# LNA.net
KiCad netlist of a schematic drawn in EAGLE
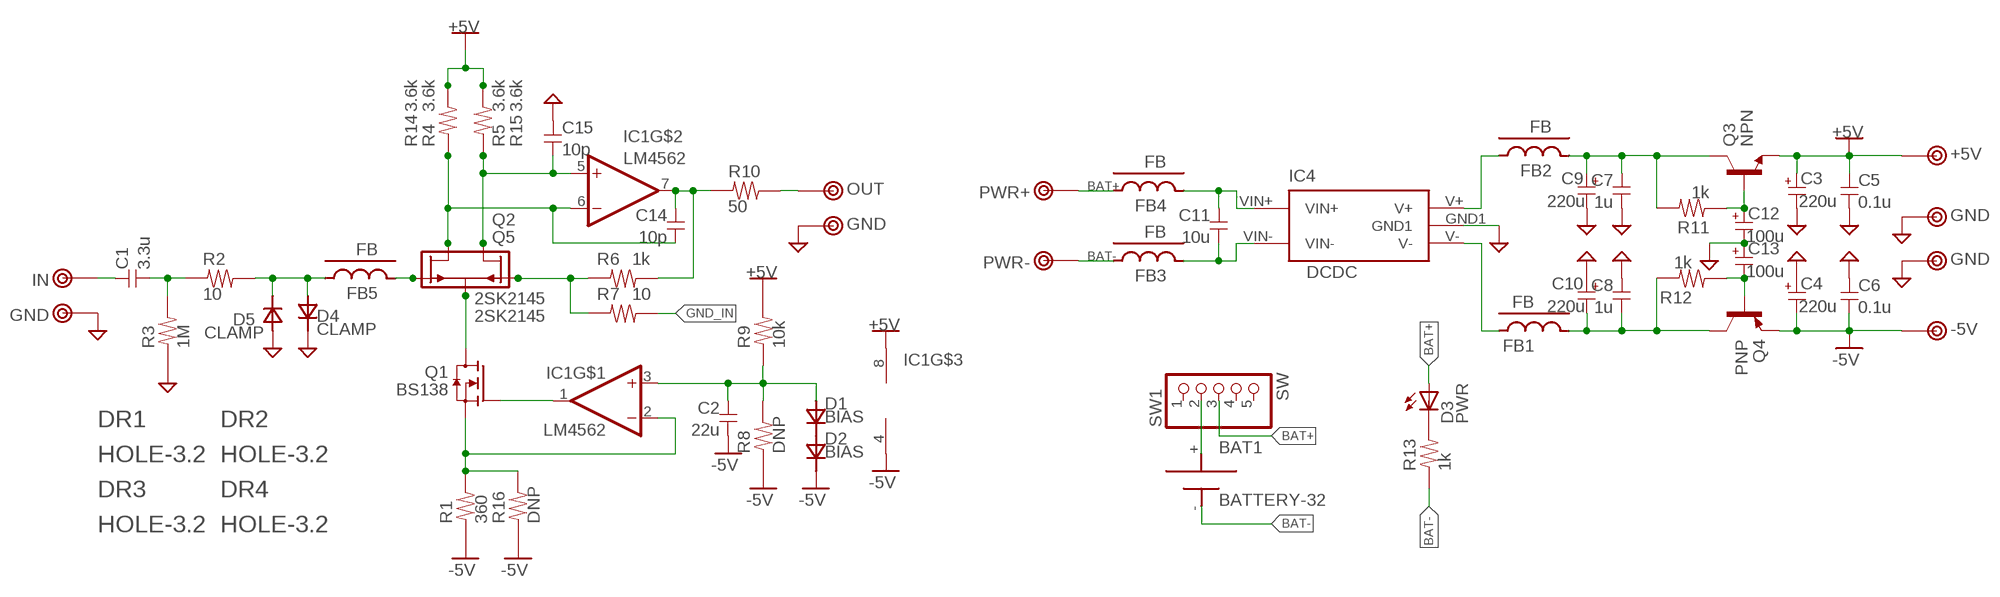
[diagram p0: schematic, sheet 1]

(export (version "E")
  (design (tool "Eeschema 10.0.6"))
  (components
    (comp (ref "BAT1")
      (value "BATTERY-32")
      (footprint "eagle-import:BH-321")
      (libsource (lib "eagle-import") (part "BATTERY-32"))
    )
    (comp (ref "C1")
      (value "3.3u")
      (footprint "eagle-import:3225")
      (libsource (lib "eagle-import") (part "C-3225"))
    )
    (comp (ref "C2")
      (value "22u")
      (footprint "eagle-import:3225")
      (libsource (lib "eagle-import") (part "C-3225"))
    )
    (comp (ref "C3")
      (value "220u")
      (footprint "eagle-import:E2,5-8")
      (libsource (lib "eagle-import") (part "CPOLE2.5-8"))
    )
    (comp (ref "C4")
      (value "220u")
      (footprint "eagle-import:E2,5-8")
      (libsource (lib "eagle-import") (part "CPOLE2.5-8"))
    )
    (comp (ref "C5")
      (value "0.1u")
      (footprint "eagle-import:1608C")
      (libsource (lib "eagle-import") (part "C-1608"))
    )
    (comp (ref "C6")
      (value "0.1u")
      (footprint "eagle-import:1608C")
      (libsource (lib "eagle-import") (part "C-1608"))
    )
    (comp (ref "C7")
      (value "1u")
      (footprint "eagle-import:1608C")
      (libsource (lib "eagle-import") (part "C-1608"))
    )
    (comp (ref "C8")
      (value "1u")
      (footprint "eagle-import:1608C")
      (libsource (lib "eagle-import") (part "C-1608"))
    )
    (comp (ref "C9")
      (value "220u")
      (footprint "eagle-import:E2,5-8")
      (libsource (lib "eagle-import") (part "CPOLE2.5-8"))
    )
    (comp (ref "C10")
      (value "220u")
      (footprint "eagle-import:E2,5-8")
      (libsource (lib "eagle-import") (part "CPOLE2.5-8"))
    )
    (comp (ref "C11")
      (value "10u")
      (footprint "eagle-import:2012")
      (libsource (lib "eagle-import") (part "C-2012"))
    )
    (comp (ref "C12")
      (value "100u")
      (footprint "eagle-import:E2.5-6.5")
      (libsource (lib "eagle-import") (part "CPOLE2.5-6.5"))
    )
    (comp (ref "C13")
      (value "100u")
      (footprint "eagle-import:E2.5-6.5")
      (libsource (lib "eagle-import") (part "CPOLE2.5-6.5"))
    )
    (comp (ref "C14")
      (value "10p")
      (footprint "eagle-import:1608C")
      (libsource (lib "eagle-import") (part "C-1608"))
    )
    (comp (ref "C15")
      (value "10p")
      (footprint "eagle-import:1608C")
      (libsource (lib "eagle-import") (part "C-1608"))
    )
    (comp (ref "D1")
      (value "BIAS")
      (footprint "eagle-import:SOD123")
      (libsource (lib "eagle-import") (part "DIODE-1N4148W"))
    )
    (comp (ref "D2")
      (value "BIAS")
      (footprint "eagle-import:SOD123")
      (libsource (lib "eagle-import") (part "DIODE-1N4148W"))
    )
    (comp (ref "D3")
      (value "PWR")
      (footprint "eagle-import:D1608")
      (libsource (lib "eagle-import") (part "LED-SMD1608"))
    )
    (comp (ref "D4")
      (value "CLAMP")
      (footprint "eagle-import:SOD323")
      (libsource (lib "eagle-import") (part "DIODE-323"))
    )
    (comp (ref "D5")
      (value "CLAMP")
      (footprint "eagle-import:SOD323")
      (libsource (lib "eagle-import") (part "DIODE-323"))
    )
    (comp (ref "DR1")
      (value "HOLE-3.2")
      (footprint "eagle-import:HOLE_3.2")
      (libsource (lib "eagle-import") (part "HOLE-3.2"))
    )
    (comp (ref "DR2")
      (value "HOLE-3.2")
      (footprint "eagle-import:HOLE_3.2")
      (libsource (lib "eagle-import") (part "HOLE-3.2"))
    )
    (comp (ref "DR3")
      (value "HOLE-3.2")
      (footprint "eagle-import:HOLE_3.2")
      (libsource (lib "eagle-import") (part "HOLE-3.2"))
    )
    (comp (ref "DR4")
      (value "HOLE-3.2")
      (footprint "eagle-import:HOLE_3.2")
      (libsource (lib "eagle-import") (part "HOLE-3.2"))
    )
    (comp (ref "FB1")
      (value "FB")
      (footprint "eagle-import:1608-FB")
      (libsource (lib "eagle-import") (part "FB-1608FB"))
    )
    (comp (ref "FB2")
      (value "FB")
      (footprint "eagle-import:1608-FB")
      (libsource (lib "eagle-import") (part "FB-1608FB"))
    )
    (comp (ref "FB3")
      (value "FB")
      (footprint "eagle-import:1608-FB")
      (libsource (lib "eagle-import") (part "FB-1608FB"))
    )
    (comp (ref "FB4")
      (value "FB")
      (footprint "eagle-import:1608-FB")
      (libsource (lib "eagle-import") (part "FB-1608FB"))
    )
    (comp (ref "FB5")
      (value "FB")
      (footprint "eagle-import:1608-FB")
      (libsource (lib "eagle-import") (part "FB-1608FB"))
    )
    (comp (ref "IC1")
      (value "LM4562")
      (footprint "eagle-import:SOP8")
      (libsource (lib "eagle-import") (part "OPA-2-SOP"))
    )
    (comp (ref "IC4")
      (value "DCDC")
      (footprint "eagle-import:DCDC2")
      (libsource (lib "eagle-import") (part "DCDC2"))
    )
    (comp (ref "Q1")
      (value "BS138")
      (footprint "eagle-import:SC59")
      (libsource (lib "eagle-import") (part "NMOS-SMD"))
    )
    (comp (ref "Q2")
      (value "2SK2145")
      (footprint "eagle-import:SOT23-5")
      (libsource (lib "eagle-import") (part "JFET-DUAL"))
    )
    (comp (ref "Q3")
      (value "NPN")
      (footprint "eagle-import:SOT223")
      (libsource (lib "eagle-import") (part "NPN-SOT223"))
    )
    (comp (ref "Q4")
      (value "PNP")
      (footprint "eagle-import:SOT223")
      (libsource (lib "eagle-import") (part "PNP-SOT223"))
    )
    (comp (ref "Q5")
      (value "2SK2145")
      (footprint "eagle-import:SOT23-5")
      (libsource (lib "eagle-import") (part "JFET-DUAL"))
    )
    (comp (ref "R1")
      (value "360")
      (footprint "eagle-import:1608")
      (libsource (lib "eagle-import") (part "R-1608"))
    )
    (comp (ref "R2")
      (value "10")
      (footprint "eagle-import:1608")
      (libsource (lib "eagle-import") (part "R-1608"))
    )
    (comp (ref "R3")
      (value "1M")
      (footprint "eagle-import:1608")
      (libsource (lib "eagle-import") (part "R-1608"))
    )
    (comp (ref "R4")
      (value "3.6k")
      (footprint "eagle-import:1608")
      (libsource (lib "eagle-import") (part "R-1608"))
    )
    (comp (ref "R5")
      (value "3.6k")
      (footprint "eagle-import:1608")
      (libsource (lib "eagle-import") (part "R-1608"))
    )
    (comp (ref "R6")
      (value "1k")
      (footprint "eagle-import:1608")
      (libsource (lib "eagle-import") (part "R-1608"))
    )
    (comp (ref "R7")
      (value "10")
      (footprint "eagle-import:1608")
      (libsource (lib "eagle-import") (part "R-1608"))
    )
    (comp (ref "R8")
      (value "DNP")
      (footprint "eagle-import:1608")
      (libsource (lib "eagle-import") (part "R-1608"))
    )
    (comp (ref "R9")
      (value "10k")
      (footprint "eagle-import:1608")
      (libsource (lib "eagle-import") (part "R-1608"))
    )
    (comp (ref "R10")
      (value "50")
      (footprint "eagle-import:1608")
      (libsource (lib "eagle-import") (part "R-1608"))
    )
    (comp (ref "R11")
      (value "1k")
      (footprint "eagle-import:1608")
      (libsource (lib "eagle-import") (part "R-1608"))
    )
    (comp (ref "R12")
      (value "1k")
      (footprint "eagle-import:1608")
      (libsource (lib "eagle-import") (part "R-1608"))
    )
    (comp (ref "R13")
      (value "1k")
      (footprint "eagle-import:1608")
      (libsource (lib "eagle-import") (part "R-1608"))
    )
    (comp (ref "R14")
      (value "3.6k")
      (footprint "eagle-import:1608")
      (libsource (lib "eagle-import") (part "R-1608"))
    )
    (comp (ref "R15")
      (value "3.6k")
      (footprint "eagle-import:1608")
      (libsource (lib "eagle-import") (part "R-1608"))
    )
    (comp (ref "R16")
      (value "DNP")
      (footprint "eagle-import:1608")
      (libsource (lib "eagle-import") (part "R-1608"))
    )
    (comp (ref "SW1")
      (value "SW")
      (footprint "eagle-import:1X05-BIG")
      (libsource (lib "eagle-import") (part "SW-1X5"))
    )
    (comp (ref "TP1")
      (value "IN")
      (footprint "eagle-import:TESTPIN")
      (libsource (lib "eagle-import") (part "TESTPIN"))
    )
    (comp (ref "TP2")
      (value "GND")
      (footprint "eagle-import:TESTPIN")
      (libsource (lib "eagle-import") (part "TESTPIN"))
    )
    (comp (ref "TP3")
      (value "OUT")
      (footprint "eagle-import:TESTPIN")
      (libsource (lib "eagle-import") (part "TESTPIN"))
    )
    (comp (ref "TP4")
      (value "GND")
      (footprint "eagle-import:TESTPIN")
      (libsource (lib "eagle-import") (part "TESTPIN"))
    )
    (comp (ref "TP5")
      (value "PWR+")
      (footprint "eagle-import:TESTPIN")
      (libsource (lib "eagle-import") (part "TESTPIN"))
    )
    (comp (ref "TP6")
      (value "PWR-")
      (footprint "eagle-import:TESTPIN")
      (libsource (lib "eagle-import") (part "TESTPIN"))
    )
    (comp (ref "TP7")
      (value "+5V")
      (footprint "eagle-import:TESTPIN-MID")
      (libsource (lib "eagle-import") (part "TESTPIN-MID"))
    )
    (comp (ref "TP8")
      (value "GND")
      (footprint "eagle-import:TESTPIN-MID")
      (libsource (lib "eagle-import") (part "TESTPIN-MID"))
    )
    (comp (ref "TP9")
      (value "GND")
      (footprint "eagle-import:TESTPIN-MID")
      (libsource (lib "eagle-import") (part "TESTPIN-MID"))
    )
    (comp (ref "TP10")
      (value "-5V")
      (footprint "eagle-import:TESTPIN-MID")
      (libsource (lib "eagle-import") (part "TESTPIN-MID"))
    )
  )
  (nets
    (net (code "1") (name "+5V") (class "Default")
      (node (ref "C3") (pin "+") (pinfunction "1_+") (pintype "passive"))
      (node (ref "C5") (pin "1") (pinfunction "1_1") (pintype "passive"))
      (node (ref "IC1") (pin "8") (pinfunction "V+_8") (pintype "input"))
      (node (ref "Q3") (pin "3") (pinfunction "E_3") (pintype "passive"))
      (node (ref "R14") (pin "2") (pinfunction "2_2") (pintype "passive"))
      (node (ref "R15") (pin "2") (pinfunction "2_2") (pintype "passive"))
      (node (ref "R4") (pin "2") (pinfunction "2_2") (pintype "passive"))
      (node (ref "R5") (pin "2") (pinfunction "2_2") (pintype "passive"))
      (node (ref "R9") (pin "2") (pinfunction "2_2") (pintype "passive"))
      (node (ref "TP7") (pin "1") (pinfunction "1_1") (pintype "passive"))
    )
    (net (code "2") (name "-5V") (class "Default")
      (node (ref "C2") (pin "2") (pinfunction "2_2") (pintype "passive"))
      (node (ref "C4") (pin "-") (pinfunction "2_-") (pintype "passive"))
      (node (ref "C6") (pin "2") (pinfunction "2_2") (pintype "passive"))
      (node (ref "D2") (pin "2") (pinfunction "K_2") (pintype "passive"))
      (node (ref "IC1") (pin "4") (pinfunction "V-_4") (pintype "input"))
      (node (ref "Q4") (pin "3") (pinfunction "E_3") (pintype "passive"))
      (node (ref "R1") (pin "1") (pinfunction "1_1") (pintype "passive"))
      (node (ref "R16") (pin "1") (pinfunction "1_1") (pintype "passive"))
      (node (ref "R8") (pin "1") (pinfunction "1_1") (pintype "passive"))
      (node (ref "TP10") (pin "1") (pinfunction "1_1") (pintype "passive"))
    )
    (net (code "3") (name "BAT+") (class "Default")
      (node (ref "D3") (pin "A") (pinfunction "A_A") (pintype "passive"))
      (node (ref "FB4") (pin "1") (pinfunction "1_1") (pintype "passive"))
      (node (ref "SW1") (pin "3") (pinfunction "3_3") (pintype "passive"))
      (node (ref "TP5") (pin "1") (pinfunction "1_1") (pintype "passive"))
    )
    (net (code "4") (name "BAT-") (class "Default")
      (node (ref "BAT1") (pin "-") (pinfunction "-_-") (pintype "power_in"))
      (node (ref "FB3") (pin "1") (pinfunction "1_1") (pintype "passive"))
      (node (ref "R13") (pin "1") (pinfunction "1_1") (pintype "passive"))
      (node (ref "TP6") (pin "1") (pinfunction "1_1") (pintype "passive"))
    )
    (net (code "5") (name "GND") (class "Default")
      (node (ref "C10") (pin "+") (pinfunction "1_+") (pintype "passive"))
      (node (ref "C12") (pin "-") (pinfunction "2_-") (pintype "passive"))
      (node (ref "C13") (pin "+") (pinfunction "1_+") (pintype "passive"))
      (node (ref "C15") (pin "1") (pinfunction "1_1") (pintype "passive"))
      (node (ref "C3") (pin "-") (pinfunction "2_-") (pintype "passive"))
      (node (ref "C4") (pin "+") (pinfunction "1_+") (pintype "passive"))
      (node (ref "C5") (pin "2") (pinfunction "2_2") (pintype "passive"))
      (node (ref "C6") (pin "1") (pinfunction "1_1") (pintype "passive"))
      (node (ref "C7") (pin "2") (pinfunction "2_2") (pintype "passive"))
      (node (ref "C8") (pin "1") (pinfunction "1_1") (pintype "passive"))
      (node (ref "C9") (pin "-") (pinfunction "2_-") (pintype "passive"))
      (node (ref "D4") (pin "2") (pinfunction "K_2") (pintype "passive"))
      (node (ref "D5") (pin "1") (pinfunction "A_1") (pintype "passive"))
      (node (ref "IC4") (pin "GND1") (pinfunction "GND1_GND1") (pintype "power_in"))
      (node (ref "R3") (pin "1") (pinfunction "1_1") (pintype "passive"))
      (node (ref "TP2") (pin "1") (pinfunction "1_1") (pintype "passive"))
      (node (ref "TP4") (pin "1") (pinfunction "1_1") (pintype "passive"))
      (node (ref "TP8") (pin "1") (pinfunction "1_1") (pintype "passive"))
      (node (ref "TP9") (pin "1") (pinfunction "1_1") (pintype "passive"))
    )
    (net (code "6") (name "GND_IN") (class "Default")
      (node (ref "R7") (pin "2") (pinfunction "2_2") (pintype "passive"))
    )
    (net (code "7") (name "Net-(BAT1-Pad+)") (class "Default")
      (node (ref "BAT1") (pin "+") (pinfunction "+_+") (pintype "power_in"))
      (node (ref "SW1") (pin "2") (pinfunction "2_2") (pintype "passive"))
    )
    (net (code "8") (name "Net-(C1-Pad1)") (class "Default")
      (node (ref "C1") (pin "1") (pinfunction "1_1") (pintype "passive"))
      (node (ref "TP1") (pin "1") (pinfunction "1_1") (pintype "passive"))
    )
    (net (code "9") (name "Net-(C1-Pad2)") (class "Default")
      (node (ref "C1") (pin "2") (pinfunction "2_2") (pintype "passive"))
      (node (ref "R2") (pin "1") (pinfunction "1_1") (pintype "passive"))
      (node (ref "R3") (pin "2") (pinfunction "2_2") (pintype "passive"))
    )
    (net (code "10") (name "Net-(C9-1)") (class "Default")
      (node (ref "C7") (pin "1") (pinfunction "1_1") (pintype "passive"))
      (node (ref "C9") (pin "+") (pinfunction "1_+") (pintype "passive"))
      (node (ref "FB2") (pin "2") (pinfunction "2_2") (pintype "passive"))
      (node (ref "Q3") (pin "2") (pinfunction "C_2") (pintype "passive"))
      (node (ref "Q3") (pin "4") (pinfunction "C_4") (pintype "passive"))
      (node (ref "R11") (pin "2") (pinfunction "2_2") (pintype "passive"))
    )
    (net (code "11") (name "Net-(C10-2)") (class "Default")
      (node (ref "C10") (pin "-") (pinfunction "2_-") (pintype "passive"))
      (node (ref "C8") (pin "2") (pinfunction "2_2") (pintype "passive"))
      (node (ref "FB1") (pin "2") (pinfunction "2_2") (pintype "passive"))
      (node (ref "Q4") (pin "2") (pinfunction "C_2") (pintype "passive"))
      (node (ref "Q4") (pin "4") (pinfunction "C_4") (pintype "passive"))
      (node (ref "R12") (pin "2") (pinfunction "2_2") (pintype "passive"))
    )
    (net (code "12") (name "Net-(C11-Pad1)") (class "Default")
      (node (ref "C11") (pin "1") (pinfunction "1_1") (pintype "passive"))
      (node (ref "FB4") (pin "2") (pinfunction "2_2") (pintype "passive"))
      (node (ref "IC4") (pin "VIN+") (pinfunction "VIN+_VIN+") (pintype "power_in"))
    )
    (net (code "13") (name "Net-(C11-Pad2)") (class "Default")
      (node (ref "C11") (pin "2") (pinfunction "2_2") (pintype "passive"))
      (node (ref "FB3") (pin "2") (pinfunction "2_2") (pintype "passive"))
      (node (ref "IC4") (pin "VIN-") (pinfunction "VIN-_VIN-") (pintype "power_in"))
    )
    (net (code "14") (name "Net-(C12-1)") (class "Default")
      (node (ref "C12") (pin "+") (pinfunction "1_+") (pintype "passive"))
      (node (ref "Q3") (pin "1") (pinfunction "B_1") (pintype "passive"))
      (node (ref "R11") (pin "1") (pinfunction "1_1") (pintype "passive"))
    )
    (net (code "15") (name "Net-(C13-2)") (class "Default")
      (node (ref "C13") (pin "-") (pinfunction "2_-") (pintype "passive"))
      (node (ref "Q4") (pin "1") (pinfunction "B_1") (pintype "passive"))
      (node (ref "R12") (pin "1") (pinfunction "1_1") (pintype "passive"))
    )
    (net (code "16") (name "Net-(D1-A)") (class "Default")
      (node (ref "C2") (pin "1") (pinfunction "1_1") (pintype "passive"))
      (node (ref "D1") (pin "1") (pinfunction "A_1") (pintype "passive"))
      (node (ref "IC1") (pin "3") (pinfunction "+IN_3") (pintype "input"))
      (node (ref "R8") (pin "2") (pinfunction "2_2") (pintype "passive"))
      (node (ref "R9") (pin "1") (pinfunction "1_1") (pintype "passive"))
    )
    (net (code "17") (name "Net-(D1-K)") (class "Default")
      (node (ref "D1") (pin "2") (pinfunction "K_2") (pintype "passive"))
      (node (ref "D2") (pin "1") (pinfunction "A_1") (pintype "passive"))
    )
    (net (code "18") (name "Net-(D3-PadK)") (class "Default")
      (node (ref "D3") (pin "K") (pinfunction "K_K") (pintype "passive"))
      (node (ref "R13") (pin "2") (pinfunction "2_2") (pintype "passive"))
    )
    (net (code "19") (name "Net-(D4-A)") (class "Default")
      (node (ref "D4") (pin "1") (pinfunction "A_1") (pintype "passive"))
      (node (ref "D5") (pin "2") (pinfunction "K_2") (pintype "passive"))
      (node (ref "FB5") (pin "1") (pinfunction "1_1") (pintype "passive"))
      (node (ref "R2") (pin "2") (pinfunction "2_2") (pintype "passive"))
    )
    (net (code "20") (name "Net-(FB1-Pad1)") (class "Default")
      (node (ref "FB1") (pin "1") (pinfunction "1_1") (pintype "passive"))
      (node (ref "IC4") (pin "V-") (pinfunction "V-_V-") (pintype "output"))
    )
    (net (code "21") (name "Net-(FB2-Pad1)") (class "Default")
      (node (ref "FB2") (pin "1") (pinfunction "1_1") (pintype "passive"))
      (node (ref "IC4") (pin "V+") (pinfunction "V+_V+") (pintype "output"))
    )
    (net (code "22") (name "Net-(IC1A--IN)") (class "Default")
      (node (ref "IC1") (pin "2") (pinfunction "-IN_2") (pintype "input"))
      (node (ref "Q1") (pin "2") (pinfunction "S_2") (pintype "passive"))
      (node (ref "R1") (pin "2") (pinfunction "2_2") (pintype "passive"))
      (node (ref "R16") (pin "2") (pinfunction "2_2") (pintype "passive"))
    )
    (net (code "23") (name "Net-(IC1A-OUT)") (class "Default")
      (node (ref "IC1") (pin "1") (pinfunction "OUT_1") (pintype "output"))
      (node (ref "Q1") (pin "1") (pinfunction "G_1") (pintype "passive"))
    )
    (net (code "24") (name "Net-(IC1B-+IN)") (class "Default")
      (node (ref "C15") (pin "2") (pinfunction "2_2") (pintype "passive"))
      (node (ref "IC1") (pin "5") (pinfunction "+IN_5") (pintype "input"))
      (node (ref "Q2") (pin "1") (pinfunction "D1_1") (pintype "passive"))
      (node (ref "Q5") (pin "3") (pinfunction "D2_3") (pintype "passive"))
      (node (ref "R15") (pin "1") (pinfunction "1_1") (pintype "passive"))
      (node (ref "R5") (pin "1") (pinfunction "1_1") (pintype "passive"))
    )
    (net (code "25") (name "Net-(IC1B--IN)") (class "Default")
      (node (ref "C14") (pin "2") (pinfunction "2_2") (pintype "passive"))
      (node (ref "IC1") (pin "6") (pinfunction "-IN_6") (pintype "input"))
      (node (ref "Q2") (pin "3") (pinfunction "D2_3") (pintype "passive"))
      (node (ref "Q5") (pin "1") (pinfunction "D1_1") (pintype "passive"))
      (node (ref "R14") (pin "1") (pinfunction "1_1") (pintype "passive"))
      (node (ref "R4") (pin "1") (pinfunction "1_1") (pintype "passive"))
    )
    (net (code "26") (name "Net-(IC1B-OUT)") (class "Default")
      (node (ref "C14") (pin "1") (pinfunction "1_1") (pintype "passive"))
      (node (ref "IC1") (pin "7") (pinfunction "OUT_7") (pintype "output"))
      (node (ref "R10") (pin "1") (pinfunction "1_1") (pintype "passive"))
      (node (ref "R6") (pin "2") (pinfunction "2_2") (pintype "passive"))
    )
    (net (code "27") (name "Net-(Q1-D)") (class "Default")
      (node (ref "Q1") (pin "3") (pinfunction "D_3") (pintype "passive"))
      (node (ref "Q2") (pin "2") (pinfunction "S_2") (pintype "passive"))
      (node (ref "Q5") (pin "2") (pinfunction "S_2") (pintype "passive"))
    )
    (net (code "28") (name "Net-(Q2-G1)") (class "Default")
      (node (ref "Q2") (pin "5") (pinfunction "G1_5") (pintype "passive"))
      (node (ref "Q5") (pin "4") (pinfunction "G2_4") (pintype "passive"))
      (node (ref "R6") (pin "1") (pinfunction "1_1") (pintype "passive"))
      (node (ref "R7") (pin "1") (pinfunction "1_1") (pintype "passive"))
    )
    (net (code "29") (name "Net-(Q2-G2)") (class "Default")
      (node (ref "FB5") (pin "2") (pinfunction "2_2") (pintype "passive"))
      (node (ref "Q2") (pin "4") (pinfunction "G2_4") (pintype "passive"))
      (node (ref "Q5") (pin "5") (pinfunction "G1_5") (pintype "passive"))
    )
    (net (code "30") (name "Net-(R10-Pad2)") (class "Default")
      (node (ref "R10") (pin "2") (pinfunction "2_2") (pintype "passive"))
      (node (ref "TP3") (pin "1") (pinfunction "1_1") (pintype "passive"))
    )
    (net (code "31") (name "unconnected-(SW1-Pad1)") (class "Default")
      (node (ref "SW1") (pin "1") (pinfunction "1_1") (pintype "passive"))
    )
    (net (code "32") (name "unconnected-(SW1-Pad4)") (class "Default")
      (node (ref "SW1") (pin "4") (pinfunction "4_4") (pintype "passive"))
    )
    (net (code "33") (name "unconnected-(SW1-Pad5)") (class "Default")
      (node (ref "SW1") (pin "5") (pinfunction "5_5") (pintype "passive"))
    )
  )
)
